# USB_ULPI_USB3320.net
KiCad netlist of a schematic drawn in Altium Designer
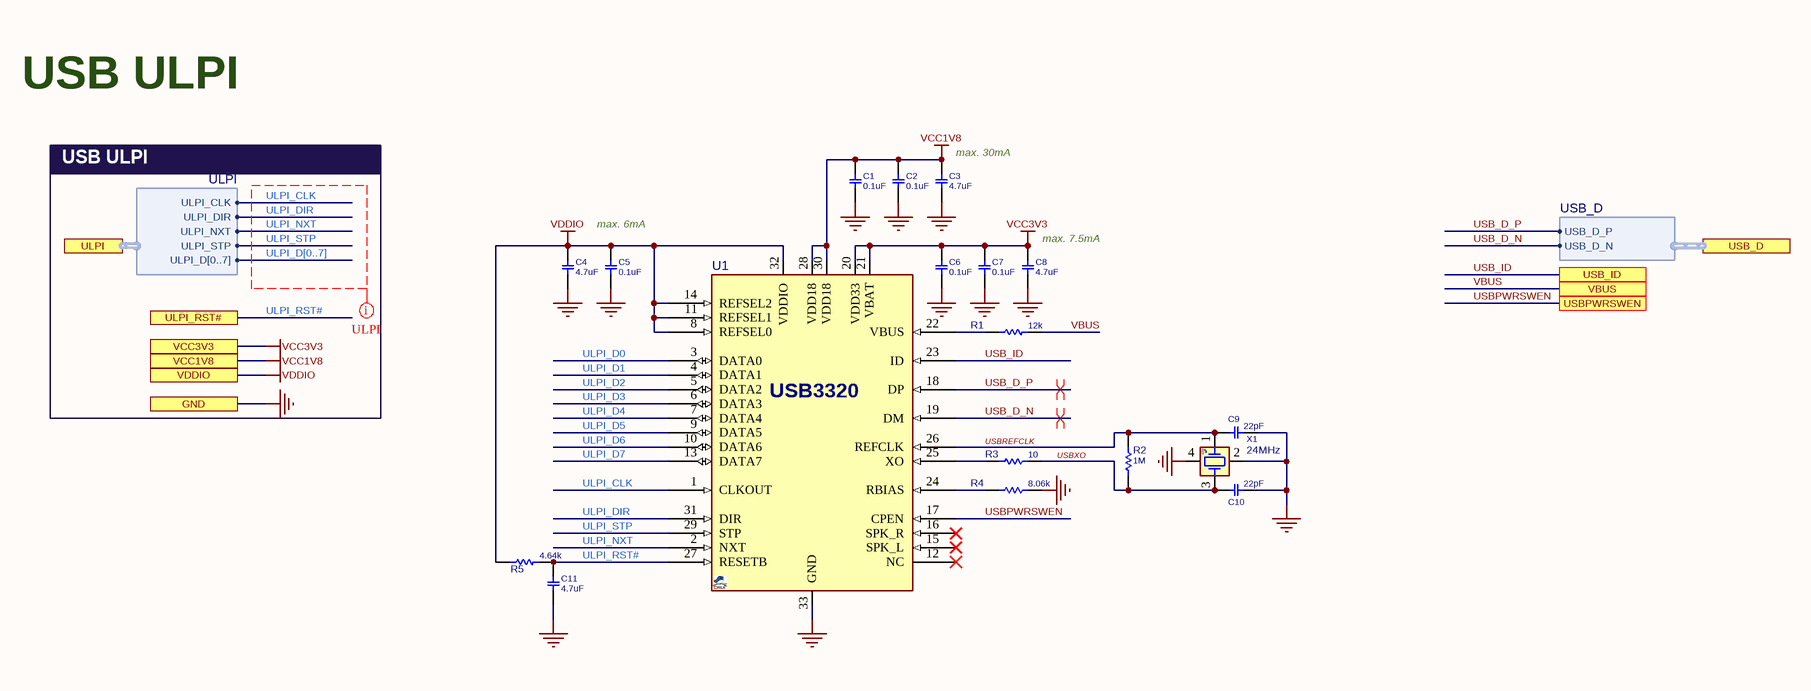
[diagram p0: USB_ULPI_USB3320.SchDoc]

(export (version "E")
  (design (tool "Eeschema 10.0.6"))
  (components
    (comp (ref "C1")
      (value "0.1uF")
      (footprint "C0402")
      (description "CAP, MLCC")
      (fields (field (name "MANF") "Murata"))
      (libsource (lib "mlcc_smd_passive") (part "CAP_SMD_MLCC_100n50TDK"))
    )
    (comp (ref "C2")
      (value "0.1uF")
      (footprint "C0402")
      (description "CAP, MLCC")
      (fields (field (name "MANF") "Murata"))
      (libsource (lib "mlcc_smd_passive") (part "CAP_SMD_MLCC_100n50TDK"))
    )
    (comp (ref "C3")
      (value "4.7uF")
      (footprint "C0402")
      (description "CAP, MLCC")
      (fields (field (name "MANF") "Murata"))
      (libsource (lib "mlcc_smd_passive") (part "CAP_SMD_MLCC_100n50TDK"))
    )
    (comp (ref "C4")
      (value "4.7uF")
      (footprint "C0402")
      (description "CAP, MLCC")
      (fields (field (name "MANF") "Murata"))
      (libsource (lib "mlcc_smd_passive") (part "CAP_SMD_MLCC_100n50TDK"))
    )
    (comp (ref "C5")
      (value "0.1uF")
      (footprint "C0402")
      (description "CAP, MLCC")
      (fields (field (name "MANF_P#") "GRM155R71H104KE14D") (field (name "MANF") "Murata"))
      (libsource (lib "mlcc_smd_passive") (part "CAP_SMD_MLCC_100n50TDK"))
    )
    (comp (ref "C6")
      (value "0.1uF")
      (footprint "C0402")
      (description "CAP, MLCC")
      (fields (field (name "MANF") "Murata"))
      (libsource (lib "mlcc_smd_passive") (part "CAP_SMD_MLCC_100n50TDK"))
    )
    (comp (ref "C7")
      (value "0.1uF")
      (footprint "C0402")
      (description "CAP, MLCC")
      (fields (field (name "MANF") "Murata"))
      (libsource (lib "mlcc_smd_passive") (part "CAP_SMD_MLCC_100n50TDK"))
    )
    (comp (ref "C8")
      (value "4.7uF")
      (footprint "C0402")
      (description "CAP, MLCC")
      (fields (field (name "MANF") "Murata"))
      (libsource (lib "mlcc_smd_passive") (part "CAP_SMD_MLCC_100n50TDK"))
    )
    (comp (ref "C9")
      (value "22pF")
      (footprint "C0402")
      (description "CAP, MLCC")
      (fields (field (name "MANF") "Murata"))
      (libsource (lib "mlcc_smd_passive") (part "CAP_SMD_MLCC_100n50TDK"))
    )
    (comp (ref "C10")
      (value "22pF")
      (footprint "C0402")
      (description "CAP, MLCC")
      (fields (field (name "MANF") "Murata"))
      (libsource (lib "mlcc_smd_passive") (part "CAP_SMD_MLCC_100n50TDK"))
    )
    (comp (ref "C11")
      (value "4.7uF")
      (footprint "C0402")
      (description "CAP, MLCC")
      (fields (field (name "MANF") "Murata"))
      (libsource (lib "mlcc_smd_passive") (part "CAP_SMD_MLCC_100n50TDK"))
    )
    (comp (ref "R1")
      (value "12k")
      (footprint "R0402")
      (description "RESISTOR, SMD")
      (libsource (lib "passive_smd") (part "RES_SMD"))
    )
    (comp (ref "R2")
      (value "1M")
      (footprint "R0402")
      (description "RESISTOR, SMD")
      (libsource (lib "passive_smd") (part "RES_SMD"))
    )
    (comp (ref "R3")
      (value "10")
      (footprint "R0402")
      (description "RESISTOR, SMD")
      (libsource (lib "passive_smd") (part "RES_SMD"))
    )
    (comp (ref "R4")
      (value "8.06k")
      (footprint "R0402")
      (description "RESISTOR, SMD")
      (libsource (lib "passive_smd") (part "RES_SMD"))
    )
    (comp (ref "R5")
      (value "4.64k")
      (footprint "R0402")
      (description "RESISTOR, SMD")
      (libsource (lib "passive_smd") (part "RES_SMD"))
    )
    (comp (ref "U1")
      (value "USB3320")
      (footprint "QFN50_32T")
      (description "USB 2.0 ULPI Transceiver")
      (fields (field (name "MANF") "SMSC") (field (name "MANF_P#") "USB3320C-EZK"))
      (libsource (lib "usbic") (part "USB3320_QFN32"))
    )
    (comp (ref "X1")
      (value "24MHz")
      (footprint "XTL_4_2016")
      (description "Crystal 24MHz")
      (fields (field (name "MANF_P#") "china"))
      (libsource (lib "crystal") (part "XTL_4_24MHz_3225"))
    )
  )
  (nets
    (net (code "3") (name "/ULPI_CLK") (class "Default")
      (node (ref "U1") (pin "1") (pinfunction "CLKOUT_1") (pintype "input"))
    )
    (net (code "4") (name "/ULPI_D0") (class "Default")
      (node (ref "U1") (pin "3") (pinfunction "DATA0_3") (pintype "bidirectional"))
    )
    (net (code "5") (name "/ULPI_D1") (class "Default")
      (node (ref "U1") (pin "4") (pinfunction "DATA1_4") (pintype "bidirectional"))
    )
    (net (code "6") (name "/ULPI_D2") (class "Default")
      (node (ref "U1") (pin "5") (pinfunction "DATA2_5") (pintype "bidirectional"))
    )
    (net (code "7") (name "/ULPI_D3") (class "Default")
      (node (ref "U1") (pin "6") (pinfunction "DATA3_6") (pintype "bidirectional"))
    )
    (net (code "8") (name "/ULPI_D4") (class "Default")
      (node (ref "U1") (pin "7") (pinfunction "DATA4_7") (pintype "bidirectional"))
    )
    (net (code "9") (name "/ULPI_D5") (class "Default")
      (node (ref "U1") (pin "9") (pinfunction "DATA5_9") (pintype "bidirectional"))
    )
    (net (code "10") (name "/ULPI_D6") (class "Default")
      (node (ref "U1") (pin "10") (pinfunction "DATA6_10") (pintype "bidirectional"))
    )
    (net (code "11") (name "/ULPI_D7") (class "Default")
      (node (ref "U1") (pin "13") (pinfunction "DATA7_13") (pintype "bidirectional"))
    )
    (net (code "12") (name "/ULPI_DIR") (class "Default")
      (node (ref "U1") (pin "31") (pinfunction "DIR_31") (pintype "input"))
    )
    (net (code "14") (name "/ULPI_NXT") (class "Default")
      (node (ref "U1") (pin "2") (pinfunction "NXT_2") (pintype "input"))
    )
    (net (code "15") (name "/ULPI_RST#") (class "Default")
      (node (ref "C11") (pin "2") (pinfunction "2_2") (pintype "passive"))
      (node (ref "R5") (pin "2") (pinfunction "2_2") (pintype "passive"))
      (node (ref "U1") (pin "27") (pinfunction "RESETB_27") (pintype "input"))
    )
    (net (code "16") (name "/ULPI_STP") (class "Default")
      (node (ref "U1") (pin "29") (pinfunction "STP_29") (pintype "input"))
    )
    (net (code "17") (name "/USBPWRSWEN") (class "Default")
      (node (ref "U1") (pin "17") (pinfunction "CPEN_17") (pintype "input"))
    )
    (net (code "18") (name "/USBREFCLK") (class "Default")
      (node (ref "C9") (pin "1") (pinfunction "1_1") (pintype "passive"))
      (node (ref "R2") (pin "2") (pinfunction "2_2") (pintype "passive"))
      (node (ref "U1") (pin "26") (pinfunction "REFCLK_26") (pintype "input"))
      (node (ref "X1") (pin "1") (pinfunction "1_1") (pintype "passive"))
    )
    (net (code "19") (name "/USBXO") (class "Default")
      (node (ref "C10") (pin "1") (pinfunction "1_1") (pintype "passive"))
      (node (ref "R2") (pin "1") (pinfunction "1_1") (pintype "passive"))
      (node (ref "R3") (pin "1") (pinfunction "1_1") (pintype "passive"))
      (node (ref "X1") (pin "3") (pinfunction "2_3") (pintype "passive"))
    )
    (net (code "20") (name "/USB_D_N") (class "Default")
      (node (ref "U1") (pin "19") (pinfunction "DM_19") (pintype "input"))
    )
    (net (code "21") (name "/USB_D_P") (class "Default")
      (node (ref "U1") (pin "18") (pinfunction "DP_18") (pintype "input"))
    )
    (net (code "22") (name "/USB_ID") (class "Default")
      (node (ref "U1") (pin "23") (pinfunction "ID_23") (pintype "input"))
    )
    (net (code "23") (name "/VBUS") (class "Default")
      (node (ref "R1") (pin "2") (pinfunction "2_2") (pintype "passive"))
    )
    (net (code "26") (name "GND") (class "Default")
      (node (ref "C1") (pin "1") (pinfunction "1_1") (pintype "passive"))
      (node (ref "C10") (pin "2") (pinfunction "2_2") (pintype "passive"))
      (node (ref "C11") (pin "1") (pinfunction "1_1") (pintype "passive"))
      (node (ref "C2") (pin "1") (pinfunction "1_1") (pintype "passive"))
      (node (ref "C3") (pin "1") (pinfunction "1_1") (pintype "passive"))
      (node (ref "C4") (pin "1") (pinfunction "1_1") (pintype "passive"))
      (node (ref "C5") (pin "2") (pinfunction "2_2") (pintype "passive"))
      (node (ref "C6") (pin "1") (pinfunction "1_1") (pintype "passive"))
      (node (ref "C7") (pin "1") (pinfunction "1_1") (pintype "passive"))
      (node (ref "C8") (pin "1") (pinfunction "1_1") (pintype "passive"))
      (node (ref "C9") (pin "2") (pinfunction "2_2") (pintype "passive"))
      (node (ref "R4") (pin "2") (pinfunction "2_2") (pintype "passive"))
      (node (ref "U1") (pin "33") (pinfunction "GND_33") (pintype "passive"))
      (node (ref "X1") (pin "2") (pinfunction "2_2") (pintype "passive"))
      (node (ref "X1") (pin "4") (pinfunction "4_4") (pintype "passive"))
    )
    (net (code "27") (name "Net-(U1-RBIAS)") (class "Default")
      (node (ref "R4") (pin "1") (pinfunction "1_1") (pintype "passive"))
      (node (ref "U1") (pin "24") (pinfunction "RBIAS_24") (pintype "input"))
    )
    (net (code "28") (name "Net-(U1-VBUS)") (class "Default")
      (node (ref "R1") (pin "1") (pinfunction "1_1") (pintype "passive"))
      (node (ref "U1") (pin "22") (pinfunction "VBUS_22") (pintype "input"))
    )
    (net (code "29") (name "Net-(U1-XO)") (class "Default")
      (node (ref "R3") (pin "2") (pinfunction "2_2") (pintype "passive"))
      (node (ref "U1") (pin "25") (pinfunction "XO_25") (pintype "input"))
    )
    (net (code "30") (name "VCC1V8") (class "Default")
      (node (ref "C1") (pin "2") (pinfunction "2_2") (pintype "passive"))
      (node (ref "C2") (pin "2") (pinfunction "2_2") (pintype "passive"))
      (node (ref "C3") (pin "2") (pinfunction "2_2") (pintype "passive"))
      (node (ref "U1") (pin "28") (pinfunction "VDD18_28") (pintype "passive"))
      (node (ref "U1") (pin "30") (pinfunction "VDD18_30") (pintype "passive"))
    )
    (net (code "31") (name "VCC3V3") (class "Default")
      (node (ref "C6") (pin "2") (pinfunction "2_2") (pintype "passive"))
      (node (ref "C7") (pin "2") (pinfunction "2_2") (pintype "passive"))
      (node (ref "C8") (pin "2") (pinfunction "2_2") (pintype "passive"))
      (node (ref "U1") (pin "20") (pinfunction "VDD33_20") (pintype "passive"))
      (node (ref "U1") (pin "21") (pinfunction "VBAT_21") (pintype "passive"))
    )
    (net (code "32") (name "VDDIO") (class "Default")
      (node (ref "C4") (pin "2") (pinfunction "2_2") (pintype "passive"))
      (node (ref "C5") (pin "1") (pinfunction "1_1") (pintype "passive"))
      (node (ref "R5") (pin "1") (pinfunction "1_1") (pintype "passive"))
      (node (ref "U1") (pin "11") (pinfunction "REFSEL1_11") (pintype "input"))
      (node (ref "U1") (pin "14") (pinfunction "REFSEL2_14") (pintype "input"))
      (node (ref "U1") (pin "32") (pinfunction "VDDIO_32") (pintype "passive"))
      (node (ref "U1") (pin "8") (pinfunction "REFSEL0_8") (pintype "input"))
    )
    (net (code "33") (name "unconnected-(U1-NC-Pad12)") (class "Default")
      (node (ref "U1") (pin "12") (pinfunction "NC_12") (pintype "passive+no_connect"))
    )
    (net (code "34") (name "unconnected-(U1-SPK_L-Pad15)") (class "Default")
      (node (ref "U1") (pin "15") (pinfunction "SPK_L_15") (pintype "input+no_connect"))
    )
    (net (code "35") (name "unconnected-(U1-SPK_R-Pad16)") (class "Default")
      (node (ref "U1") (pin "16") (pinfunction "SPK_R_16") (pintype "input+no_connect"))
    )
  )
)
